# WiiExt.net
KiCad netlist of a schematic drawn in EAGLE
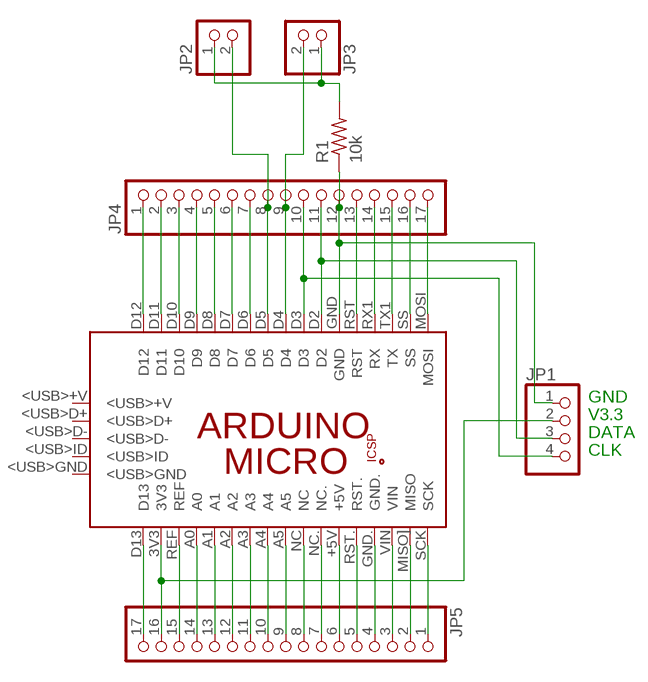
[diagram p0: schematic, sheet 1]

(export (version "E")
  (design (tool "Eeschema 10.0.6"))
  (components
    (comp (ref "JP1")
      (value "PINHD-1X4")
      (footprint "eagle-import:1X04")
      (libsource (lib "eagle-import") (part "PINHD-1X4"))
    )
    (comp (ref "JP2")
      (value "PINHD-1X2")
      (footprint "eagle-import:1X02")
      (libsource (lib "eagle-import") (part "PINHD-1X2"))
    )
    (comp (ref "JP3")
      (value "PINHD-1X2")
      (footprint "eagle-import:1X02")
      (libsource (lib "eagle-import") (part "PINHD-1X2"))
    )
    (comp (ref "JP4")
      (value "PINHD-1X17")
      (footprint "eagle-import:1X17")
      (libsource (lib "eagle-import") (part "PINHD-1X17"))
    )
    (comp (ref "JP5")
      (value "PINHD-1X17")
      (footprint "eagle-import:1X17")
      (libsource (lib "eagle-import") (part "PINHD-1X17"))
    )
    (comp (ref "PCB1")
      (value "ARDUINO_MICROOUTLINE")
      (footprint "eagle-import:ARDUINO_MICRO")
      (libsource (lib "eagle-import") (part "ARDUINO_MICROOUTLINE"))
    )
    (comp (ref "R1")
      (value "10k")
      (footprint "eagle-import:0204_7")
      (libsource (lib "eagle-import") (part "R-US_0204/7"))
    )
  )
  (nets
    (net (code "1") (name "Net-(JP1-Pad1)") (class "Default")
      (node (ref "JP1") (pin "1") (pinfunction "1_1") (pintype "passive"))
      (node (ref "JP4") (pin "12") (pinfunction "12_12") (pintype "passive"))
      (node (ref "PCB1") (pin "GND") (pinfunction "GND_GND") (pintype "bidirectional"))
      (node (ref "R1") (pin "1") (pinfunction "1_1") (pintype "passive"))
    )
    (net (code "2") (name "Net-(JP1-Pad2)") (class "Default")
      (node (ref "JP1") (pin "2") (pinfunction "2_2") (pintype "passive"))
      (node (ref "JP5") (pin "16") (pinfunction "16_16") (pintype "passive"))
      (node (ref "PCB1") (pin "3V3") (pinfunction "3V3_3V3") (pintype "bidirectional"))
    )
    (net (code "3") (name "Net-(JP1-Pad3)") (class "Default")
      (node (ref "JP1") (pin "3") (pinfunction "3_3") (pintype "passive"))
      (node (ref "JP4") (pin "11") (pinfunction "11_11") (pintype "passive"))
      (node (ref "PCB1") (pin "D2") (pinfunction "D2_D2") (pintype "bidirectional"))
    )
    (net (code "4") (name "Net-(JP1-Pad4)") (class "Default")
      (node (ref "JP1") (pin "4") (pinfunction "4_4") (pintype "passive"))
      (node (ref "JP4") (pin "10") (pinfunction "10_10") (pintype "passive"))
      (node (ref "PCB1") (pin "D3") (pinfunction "D3_D3") (pintype "bidirectional"))
    )
    (net (code "5") (name "Net-(JP2-Pad1)") (class "Default")
      (node (ref "JP2") (pin "1") (pinfunction "1_1") (pintype "passive"))
      (node (ref "JP3") (pin "1") (pinfunction "1_1") (pintype "passive"))
      (node (ref "R1") (pin "2") (pinfunction "2_2") (pintype "passive"))
    )
    (net (code "6") (name "Net-(JP2-Pad2)") (class "Default")
      (node (ref "JP2") (pin "2") (pinfunction "2_2") (pintype "passive"))
      (node (ref "JP4") (pin "8") (pinfunction "8_8") (pintype "passive"))
      (node (ref "PCB1") (pin "D5") (pinfunction "D5_D5") (pintype "bidirectional"))
    )
    (net (code "7") (name "Net-(JP3-Pad2)") (class "Default")
      (node (ref "JP3") (pin "2") (pinfunction "2_2") (pintype "passive"))
      (node (ref "JP4") (pin "9") (pinfunction "9_9") (pintype "passive"))
      (node (ref "PCB1") (pin "D4") (pinfunction "D4_D4") (pintype "bidirectional"))
    )
    (net (code "8") (name "Net-(JP4-Pad1)") (class "Default")
      (node (ref "JP4") (pin "1") (pinfunction "1_1") (pintype "passive"))
      (node (ref "PCB1") (pin "D12") (pinfunction "D12_D12") (pintype "bidirectional"))
    )
    (net (code "9") (name "Net-(JP4-Pad2)") (class "Default")
      (node (ref "JP4") (pin "2") (pinfunction "2_2") (pintype "passive"))
      (node (ref "PCB1") (pin "D11") (pinfunction "D11_D11") (pintype "bidirectional"))
    )
    (net (code "10") (name "Net-(JP4-Pad3)") (class "Default")
      (node (ref "JP4") (pin "3") (pinfunction "3_3") (pintype "passive"))
      (node (ref "PCB1") (pin "D10") (pinfunction "D10_D10") (pintype "bidirectional"))
    )
    (net (code "11") (name "Net-(JP4-Pad4)") (class "Default")
      (node (ref "JP4") (pin "4") (pinfunction "4_4") (pintype "passive"))
      (node (ref "PCB1") (pin "D9") (pinfunction "D9_D9") (pintype "bidirectional"))
    )
    (net (code "12") (name "Net-(JP4-Pad5)") (class "Default")
      (node (ref "JP4") (pin "5") (pinfunction "5_5") (pintype "passive"))
      (node (ref "PCB1") (pin "D8") (pinfunction "D8_D8") (pintype "bidirectional"))
    )
    (net (code "13") (name "Net-(JP4-Pad6)") (class "Default")
      (node (ref "JP4") (pin "6") (pinfunction "6_6") (pintype "passive"))
      (node (ref "PCB1") (pin "D7") (pinfunction "D7_D7") (pintype "bidirectional"))
    )
    (net (code "14") (name "Net-(JP4-Pad7)") (class "Default")
      (node (ref "JP4") (pin "7") (pinfunction "7_7") (pintype "passive"))
      (node (ref "PCB1") (pin "D6") (pinfunction "D6_D6") (pintype "bidirectional"))
    )
    (net (code "15") (name "Net-(JP4-Pad13)") (class "Default")
      (node (ref "JP4") (pin "13") (pinfunction "13_13") (pintype "passive"))
      (node (ref "PCB1") (pin "RST") (pinfunction "RST_RST") (pintype "bidirectional"))
    )
    (net (code "16") (name "Net-(JP4-Pad16)") (class "Default")
      (node (ref "JP4") (pin "16") (pinfunction "16_16") (pintype "passive"))
      (node (ref "PCB1") (pin "SS") (pinfunction "SS_SS") (pintype "bidirectional"))
    )
    (net (code "17") (name "Net-(JP4-Pad17)") (class "Default")
      (node (ref "JP4") (pin "17") (pinfunction "17_17") (pintype "passive"))
      (node (ref "PCB1") (pin "MOSI") (pinfunction "MOSI_MOSI") (pintype "bidirectional"))
    )
    (net (code "18") (name "Net-(JP5-Pad1)") (class "Default")
      (node (ref "JP5") (pin "1") (pinfunction "1_1") (pintype "passive"))
      (node (ref "PCB1") (pin "SCK") (pinfunction "SCK_SCK") (pintype "bidirectional"))
    )
    (net (code "19") (name "Net-(JP5-Pad3)") (class "Default")
      (node (ref "JP5") (pin "3") (pinfunction "3_3") (pintype "passive"))
      (node (ref "PCB1") (pin "VIN") (pinfunction "VIN_VIN") (pintype "bidirectional"))
    )
    (net (code "20") (name "Net-(JP5-Pad4)") (class "Default")
      (node (ref "JP5") (pin "4") (pinfunction "4_4") (pintype "passive"))
      (node (ref "PCB1") (pin "GND.") (pinfunction "GND._GND.") (pintype "bidirectional"))
    )
    (net (code "21") (name "Net-(JP5-Pad5)") (class "Default")
      (node (ref "JP5") (pin "5") (pinfunction "5_5") (pintype "passive"))
      (node (ref "PCB1") (pin "RST.") (pinfunction "RST._RST.") (pintype "bidirectional"))
    )
    (net (code "22") (name "Net-(JP5-Pad6)") (class "Default")
      (node (ref "JP5") (pin "6") (pinfunction "6_6") (pintype "passive"))
      (node (ref "PCB1") (pin "+5V") (pinfunction "+5V_+5V") (pintype "bidirectional"))
    )
    (net (code "23") (name "Net-(JP5-Pad7)") (class "Default")
      (node (ref "JP5") (pin "7") (pinfunction "7_7") (pintype "passive"))
      (node (ref "PCB1") (pin "NC.") (pinfunction "NC._NC.") (pintype "bidirectional"))
    )
    (net (code "24") (name "Net-(JP5-Pad8)") (class "Default")
      (node (ref "JP5") (pin "8") (pinfunction "8_8") (pintype "passive"))
      (node (ref "PCB1") (pin "NC") (pinfunction "NC_NC") (pintype "bidirectional"))
    )
    (net (code "25") (name "Net-(JP5-Pad9)") (class "Default")
      (node (ref "JP5") (pin "9") (pinfunction "9_9") (pintype "passive"))
      (node (ref "PCB1") (pin "A5") (pinfunction "A5_A5") (pintype "bidirectional"))
    )
    (net (code "26") (name "Net-(JP5-Pad10)") (class "Default")
      (node (ref "JP5") (pin "10") (pinfunction "10_10") (pintype "passive"))
      (node (ref "PCB1") (pin "A4") (pinfunction "A4_A4") (pintype "bidirectional"))
    )
    (net (code "27") (name "Net-(JP5-Pad11)") (class "Default")
      (node (ref "JP5") (pin "11") (pinfunction "11_11") (pintype "passive"))
      (node (ref "PCB1") (pin "A3") (pinfunction "A3_A3") (pintype "bidirectional"))
    )
    (net (code "28") (name "Net-(JP5-Pad12)") (class "Default")
      (node (ref "JP5") (pin "12") (pinfunction "12_12") (pintype "passive"))
      (node (ref "PCB1") (pin "A2") (pinfunction "A2_A2") (pintype "bidirectional"))
    )
    (net (code "29") (name "Net-(JP5-Pad13)") (class "Default")
      (node (ref "JP5") (pin "13") (pinfunction "13_13") (pintype "passive"))
      (node (ref "PCB1") (pin "A1") (pinfunction "A1_A1") (pintype "bidirectional"))
    )
    (net (code "30") (name "Net-(JP5-Pad14)") (class "Default")
      (node (ref "JP5") (pin "14") (pinfunction "14_14") (pintype "passive"))
      (node (ref "PCB1") (pin "A0") (pinfunction "A0_A0") (pintype "bidirectional"))
    )
    (net (code "31") (name "Net-(JP5-Pad15)") (class "Default")
      (node (ref "JP5") (pin "15") (pinfunction "15_15") (pintype "passive"))
      (node (ref "PCB1") (pin "REF") (pinfunction "REF_REF") (pintype "bidirectional"))
    )
    (net (code "32") (name "Net-(JP5-Pad17)") (class "Default")
      (node (ref "JP5") (pin "17") (pinfunction "17_17") (pintype "passive"))
      (node (ref "PCB1") (pin "D13") (pinfunction "D13_D13") (pintype "bidirectional"))
    )
    (net (code "33") (name "Net-(PCB1-MISO)") (class "Default")
      (node (ref "JP5") (pin "2") (pinfunction "2_2") (pintype "passive"))
      (node (ref "PCB1") (pin "MISO]") (pinfunction "MISO_MISO]") (pintype "bidirectional"))
    )
    (net (code "34") (name "Net-(PCB1-RX)") (class "Default")
      (node (ref "JP4") (pin "14") (pinfunction "14_14") (pintype "passive"))
      (node (ref "PCB1") (pin "RX1") (pinfunction "RX_RX1") (pintype "bidirectional"))
    )
    (net (code "35") (name "Net-(PCB1-TX)") (class "Default")
      (node (ref "JP4") (pin "15") (pinfunction "15_15") (pintype "passive"))
      (node (ref "PCB1") (pin "TX1") (pinfunction "TX_TX1") (pintype "bidirectional"))
    )
    (net (code "36") (name "unconnected-(PCB1-Pad5V)") (class "Default")
      (node (ref "PCB1") (pin "5V") (pinfunction "5V_5V") (pintype "bidirectional"))
    )
    (net (code "37") (name "unconnected-(PCB1-Pad<USB>+V)") (class "Default")
      (node (ref "PCB1") (pin "<USB>+V") (pinfunction "<USB>+V_<USB>+V") (pintype "bidirectional"))
    )
    (net (code "38") (name "unconnected-(PCB1-Pad<USB>D+)") (class "Default")
      (node (ref "PCB1") (pin "<USB>D+") (pinfunction "<USB>D+_<USB>D+") (pintype "bidirectional"))
    )
    (net (code "39") (name "unconnected-(PCB1-Pad<USB>D-)") (class "Default")
      (node (ref "PCB1") (pin "<USB>D-") (pinfunction "<USB>D-_<USB>D-") (pintype "bidirectional"))
    )
    (net (code "40") (name "unconnected-(PCB1-Pad<USB>GND)") (class "Default")
      (node (ref "PCB1") (pin "<USB>GND") (pinfunction "<USB>GND_<USB>GND") (pintype "bidirectional"))
    )
    (net (code "41") (name "unconnected-(PCB1-Pad<USB>ID)") (class "Default")
      (node (ref "PCB1") (pin "<USB>ID") (pinfunction "<USB>ID_<USB>ID") (pintype "bidirectional"))
    )
    (net (code "42") (name "unconnected-(PCB1-PadGND_)") (class "Default")
      (node (ref "PCB1") (pin "GND_") (pinfunction "GND__GND_") (pintype "bidirectional"))
    )
    (net (code "43") (name "unconnected-(PCB1-PadMISO.)") (class "Default")
      (node (ref "PCB1") (pin "MISO.") (pinfunction "MISO._MISO.") (pintype "bidirectional"))
    )
    (net (code "44") (name "unconnected-(PCB1-PadMOSI.)") (class "Default")
      (node (ref "PCB1") (pin "MOSI.") (pinfunction "MOSI._MOSI.") (pintype "bidirectional"))
    )
    (net (code "45") (name "unconnected-(PCB1-PadRESET..)") (class "Default")
      (node (ref "PCB1") (pin "RESET..") (pinfunction "RESET.._RESET..") (pintype "bidirectional"))
    )
    (net (code "46") (name "unconnected-(PCB1-PadSCK.)") (class "Default")
      (node (ref "PCB1") (pin "SCK.") (pinfunction "SCK._SCK.") (pintype "bidirectional"))
    )
  )
)
